# STM32_Schematic.net
KiCad netlist of a schematic drawn in Altium Designer
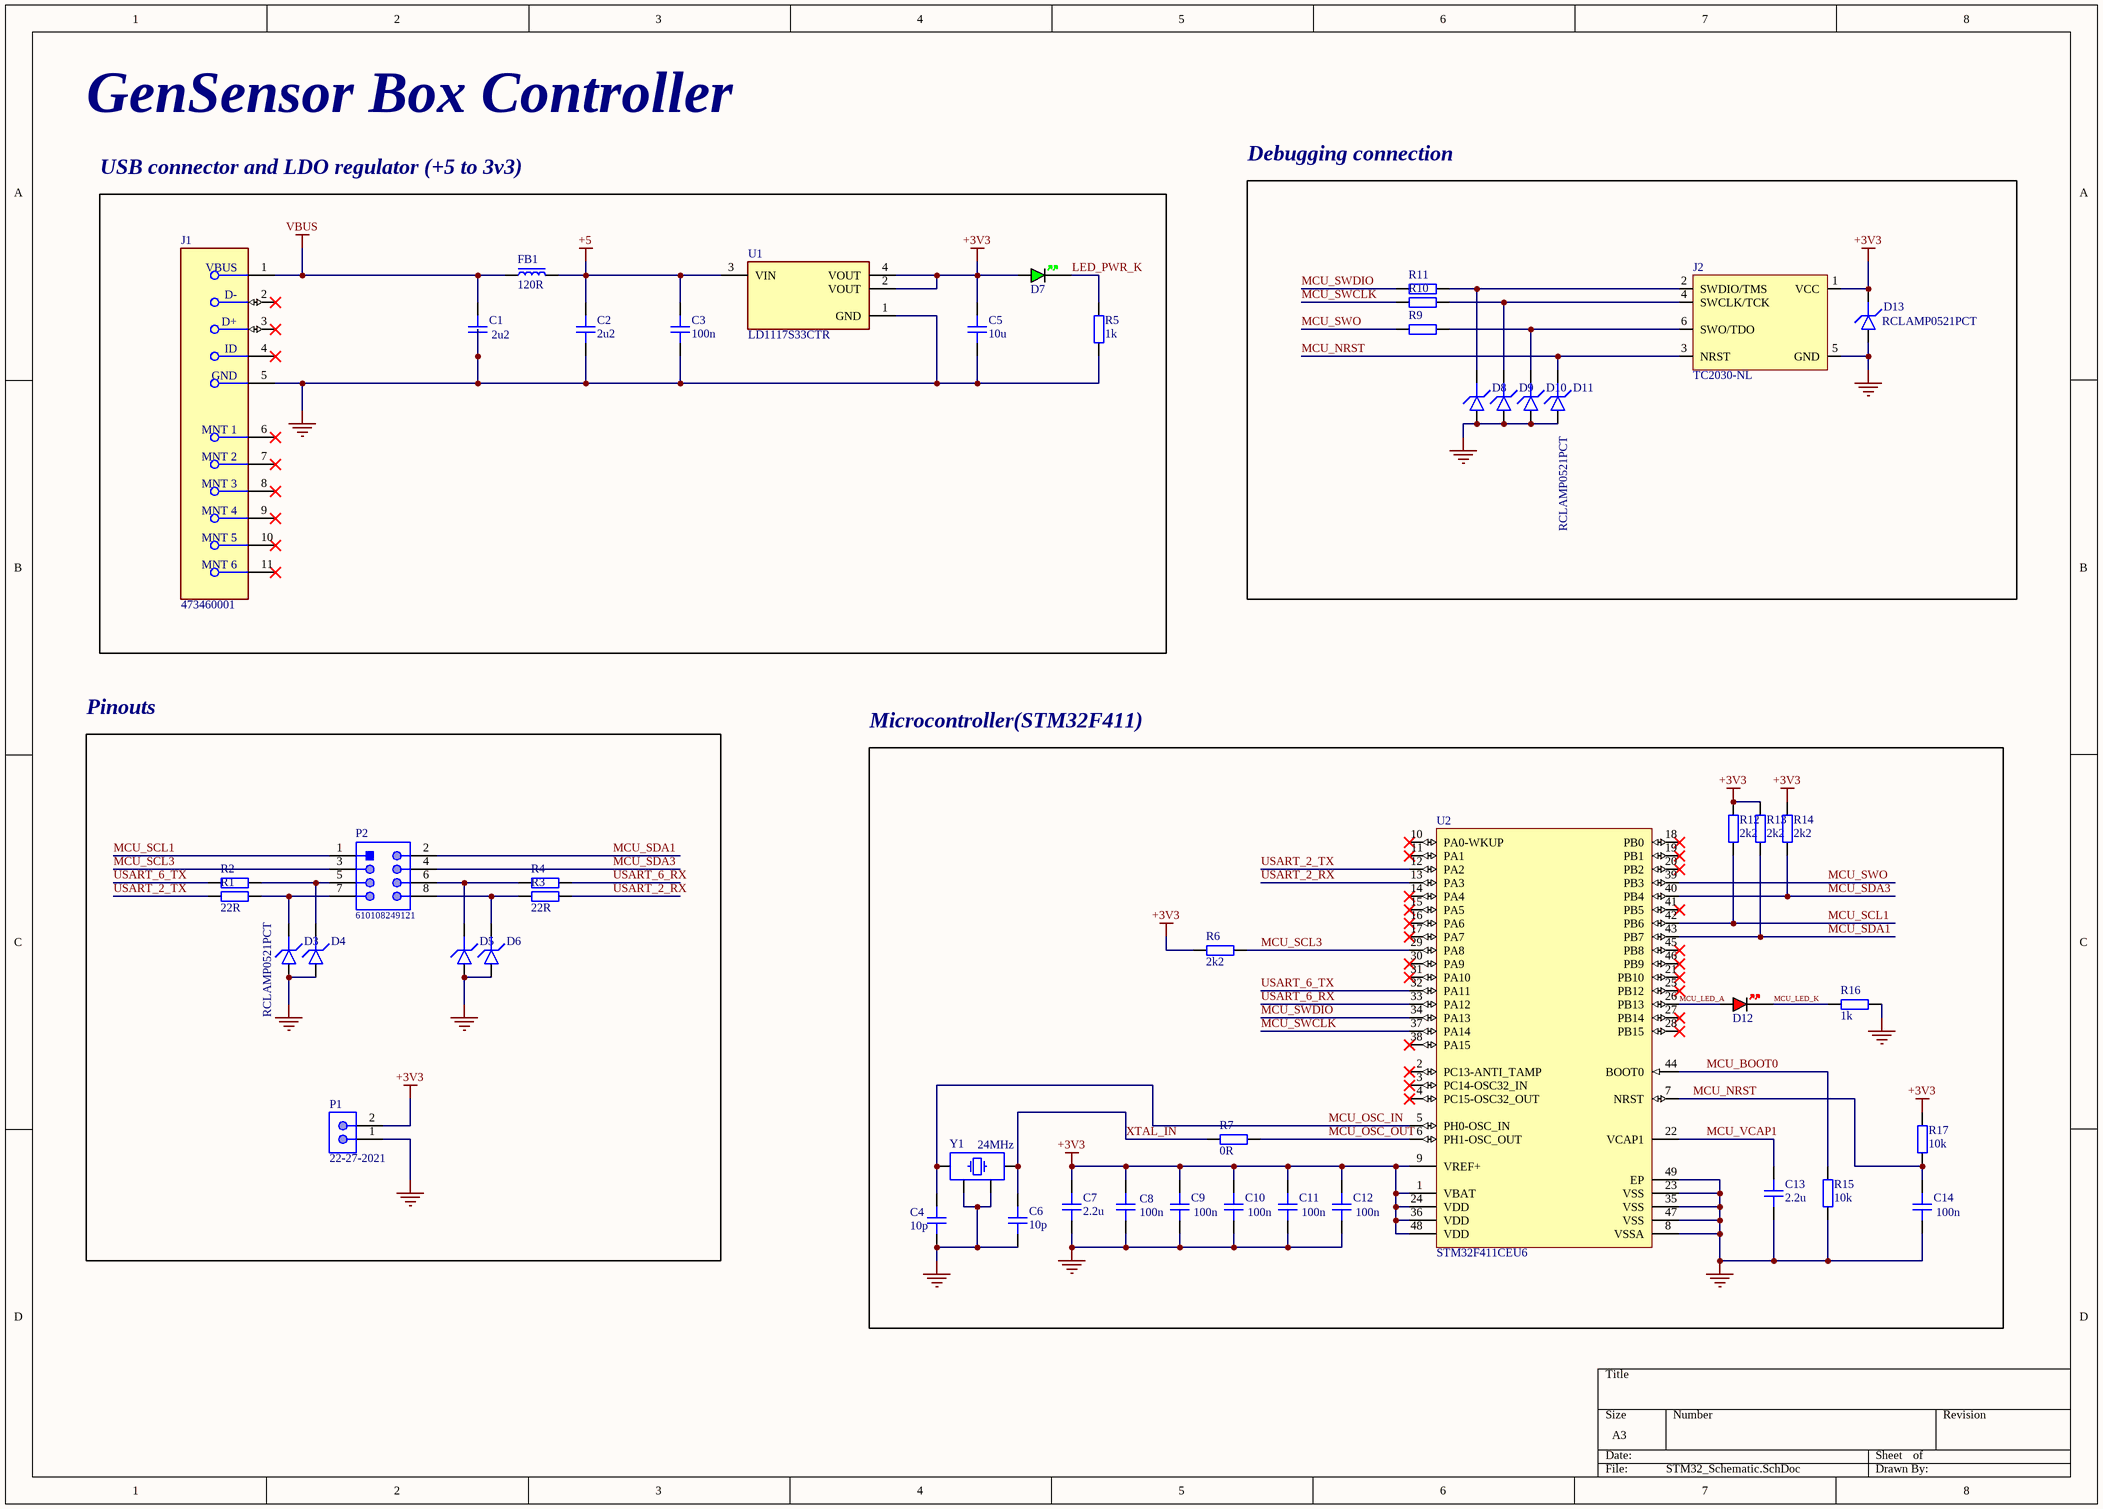
[diagram p0: STM32_Schematic.SchDoc]

(export (version "E")
  (design (tool "Eeschema 10.0.6"))
  (components
    (comp (ref "C1")
      (value "2u2")
      (footprint "CAP_0603")
      (description "Capacitor SMD 0603 16V")
      (libsource (lib "Schematic-Lib-PhilsLab") (part "CAP_0603_16V"))
    )
    (comp (ref "C2")
      (value "2u2")
      (footprint "CAP_0603")
      (description "Capacitor SMD 0603 16V")
      (libsource (lib "Schematic-Lib-PhilsLab") (part "CAP_0603_16V"))
    )
    (comp (ref "C3")
      (value "100n")
      (footprint "CAP_0805")
      (description "Capacitor SMD 0805 16V")
      (libsource (lib "Schematic-Lib-PhilsLab") (part "CAP_0805_16V"))
    )
    (comp (ref "C4")
      (value "10p")
      (footprint "CAP_0402")
      (description "Capacitor SMD 0402 16V")
      (libsource (lib "Schematic-Lib-PhilsLab") (part "CAP_0402_16V"))
    )
    (comp (ref "C5")
      (value "10u")
      (footprint "CAP_0805")
      (description "Capacitor SMD 0805 16V")
      (libsource (lib "Schematic-Lib-PhilsLab") (part "CAP_0805_16V"))
    )
    (comp (ref "C6")
      (value "10p")
      (footprint "CAP_0402")
      (description "Capacitor SMD 0402 16V")
      (libsource (lib "Schematic-Lib-PhilsLab") (part "CAP_0402_16V"))
    )
    (comp (ref "C7")
      (value "2.2u")
      (footprint "CAP_0603")
      (description "Capacitor SMD 0603 16V")
      (libsource (lib "Schematic-Lib-PhilsLab") (part "CAP_0603_16V"))
    )
    (comp (ref "C8")
      (value "100n")
      (footprint "CAP_0402")
      (description "Capacitor SMD 0402 16V")
      (libsource (lib "Schematic-Lib-PhilsLab") (part "CAP_0402_16V"))
    )
    (comp (ref "C9")
      (value "100n")
      (footprint "CAP_0402")
      (description "Capacitor SMD 0402 16V")
      (libsource (lib "Schematic-Lib-PhilsLab") (part "CAP_0402_16V"))
    )
    (comp (ref "C10")
      (value "100n")
      (footprint "CAP_0402")
      (description "Capacitor SMD 0402 16V")
      (libsource (lib "Schematic-Lib-PhilsLab") (part "CAP_0402_16V"))
    )
    (comp (ref "C11")
      (value "100n")
      (footprint "CAP_0402")
      (description "Capacitor SMD 0402 16V")
      (libsource (lib "Schematic-Lib-PhilsLab") (part "CAP_0402_16V"))
    )
    (comp (ref "C12")
      (value "100n")
      (footprint "CAP_0402")
      (description "Capacitor SMD 0402 16V")
      (libsource (lib "Schematic-Lib-PhilsLab") (part "CAP_0402_16V"))
    )
    (comp (ref "C13")
      (value "2.2u")
      (footprint "CAP_0603")
      (description "Capacitor SMD 0603 16V")
      (libsource (lib "Schematic-Lib-PhilsLab") (part "CAP_0603_16V"))
    )
    (comp (ref "C14")
      (value "100n")
      (footprint "CAP_0402")
      (description "Capacitor SMD 0402 16V")
      (libsource (lib "Schematic-Lib-PhilsLab") (part "CAP_0402_16V"))
    )
    (comp (ref "D3")
      (value "RCLAMP0521PCT")
      (footprint "D_0402")
      (description "Diode TVS / ESD 0402")
      (libsource (lib "Schematic-Lib-PhilsLab") (part "D_TVS_0402"))
    )
    (comp (ref "D4")
      (value "RCLAMP0521PCT")
      (footprint "D_0402")
      (description "Diode TVS / ESD 0402")
      (libsource (lib "Schematic-Lib-PhilsLab") (part "D_TVS_0402"))
    )
    (comp (ref "D5")
      (value "RCLAMP0521PCT")
      (footprint "D_0402")
      (description "Diode TVS / ESD 0402")
      (libsource (lib "Schematic-Lib-PhilsLab") (part "D_TVS_0402"))
    )
    (comp (ref "D6")
      (value "RCLAMP0521PCT")
      (footprint "D_0402")
      (description "Diode TVS / ESD 0402")
      (libsource (lib "Schematic-Lib-PhilsLab") (part "D_TVS_0402"))
    )
    (comp (ref "D7")
      (value "GREEN")
      (footprint "LED_0402_GREEN")
      (description "LED 0402 GREEN SMD")
      (libsource (lib "Schematic-Lib-PhilsLab") (part "LED_0402_GREEN"))
    )
    (comp (ref "D8")
      (value "RCLAMP0521PCT")
      (footprint "D_0402")
      (description "Diode TVS / ESD 0402")
      (libsource (lib "Schematic-Lib-PhilsLab") (part "D_TVS_0402"))
    )
    (comp (ref "D9")
      (value "RCLAMP0521PCT")
      (footprint "D_0402")
      (description "Diode TVS / ESD 0402")
      (libsource (lib "Schematic-Lib-PhilsLab") (part "D_TVS_0402"))
    )
    (comp (ref "D10")
      (value "RCLAMP0521PCT")
      (footprint "D_0402")
      (description "Diode TVS / ESD 0402")
      (libsource (lib "Schematic-Lib-PhilsLab") (part "D_TVS_0402"))
    )
    (comp (ref "D11")
      (value "RCLAMP0521PCT")
      (footprint "D_0402")
      (description "Diode TVS / ESD 0402")
      (libsource (lib "Schematic-Lib-PhilsLab") (part "D_TVS_0402"))
    )
    (comp (ref "D12")
      (value "RED")
      (footprint "LED_0402_RED")
      (description "LED 0402 RED SMD")
      (libsource (lib "Schematic-Lib-PhilsLab") (part "LED_0402_RED"))
    )
    (comp (ref "D13")
      (value "RCLAMP0521PCT")
      (footprint "D_0402")
      (description "Diode TVS / ESD 0402")
      (libsource (lib "Schematic-Lib-PhilsLab") (part "D_TVS_0402"))
    )
    (comp (ref "FB1")
      (value "120R")
      (footprint "FB_0603")
      (description "Ferrite Bead SMD 0603")
      (libsource (lib "Schematic-Lib-PhilsLab") (part "FB_0603"))
    )
    (comp (ref "J1")
      (value "473460001")
      (footprint "FP-473460001-MFG")
      (description "CONN RCPT USB2.0 MICRO B SMD R/A")
      (fields
        (field (name "OCTOPART") "https://octopart.com/47346-0001-molex-7164928")
        (field (name "MANUFACTURER") "Molex")
      )
      (libsource (lib "Altium Content Vault") (part "53ae1f1d9b557310b43ca686e5bb76a"))
    )
    (comp (ref "J2")
      (value "TC2030-NL")
      (footprint "TC2030-NL-FP")
      (description "Tag-Connect No-Solder SWD Debug Connector (No Legs) DO NOT PLACE")
      (fields
        (field (name "MANUFACTURER") "Tag-Connect")
        (field (name "MANUFACTURER PART NUMBER") "TC2030-NL-FP")
      )
      (libsource (lib "Schematic-Lib-PhilsLab") (part "TC2030-NL"))
    )
    (comp (ref "P1")
      (value "22-27-2021")
      (footprint "MOLX-22-27-2021_V")
      (fields (field (name "MANUFACTURER") "Molex") (field (name "PARTNUMBER") "0022272021"))
      (libsource (lib "Altium Content Vault") (part "CN-1P-M-R2"))
    )
    (comp (ref "P2")
      (value "610108249121")
      (footprint "610108249121")
      (description "SMT Angled Pin Header WR-PHD, Pitch 2.54 mm, Dual Row, 8 pins")
      (fields (field (name "MANUFACTURER") "Wurth Elektronik") (field (name "PUBLISHER") "WurthElektronik"))
      (libsource (lib "Altium Content Vault") (part "WE-CN-2P-M-R8"))
    )
    (comp (ref "R1")
      (value "22R")
      (footprint "RES_0402")
      (description "Resistor SMD 0402")
      (libsource (lib "Schematic-Lib-PhilsLab") (part "RES_0402"))
    )
    (comp (ref "R2")
      (value "22R")
      (footprint "RES_0402")
      (description "Resistor SMD 0402")
      (libsource (lib "Schematic-Lib-PhilsLab") (part "RES_0402"))
    )
    (comp (ref "R3")
      (value "22R")
      (footprint "RES_0402")
      (description "Resistor SMD 0402")
      (libsource (lib "Schematic-Lib-PhilsLab") (part "RES_0402"))
    )
    (comp (ref "R4")
      (value "22R")
      (footprint "RES_0402")
      (description "Resistor SMD 0402")
      (libsource (lib "Schematic-Lib-PhilsLab") (part "RES_0402"))
    )
    (comp (ref "R5")
      (value "1k")
      (footprint "RES_0402")
      (description "Resistor SMD 0402")
      (libsource (lib "Schematic-Lib-PhilsLab") (part "RES_0402"))
    )
    (comp (ref "R6")
      (value "2k2")
      (footprint "RES_0402")
      (description "Resistor SMD 0402")
      (libsource (lib "Schematic-Lib-PhilsLab") (part "RES_0402"))
    )
    (comp (ref "R7")
      (value "0R")
      (footprint "RES_0402")
      (description "Resistor SMD 0402")
      (libsource (lib "Schematic-Lib-PhilsLab") (part "RES_0402"))
    )
    (comp (ref "R9")
      (value "22R")
      (footprint "RES_0402")
      (description "Resistor SMD 0402")
      (libsource (lib "Schematic-Lib-PhilsLab") (part "RES_0402"))
    )
    (comp (ref "R10")
      (value "22R")
      (footprint "RES_0402")
      (description "Resistor SMD 0402")
      (libsource (lib "Schematic-Lib-PhilsLab") (part "RES_0402"))
    )
    (comp (ref "R11")
      (value "22R")
      (footprint "RES_0402")
      (description "Resistor SMD 0402")
      (libsource (lib "Schematic-Lib-PhilsLab") (part "RES_0402"))
    )
    (comp (ref "R12")
      (value "2k2")
      (footprint "RES_0402")
      (description "Resistor SMD 0402")
      (libsource (lib "Schematic-Lib-PhilsLab") (part "RES_0402"))
    )
    (comp (ref "R13")
      (value "2k2")
      (footprint "RES_0402")
      (description "Resistor SMD 0402")
      (libsource (lib "Schematic-Lib-PhilsLab") (part "RES_0402"))
    )
    (comp (ref "R14")
      (value "2k2")
      (footprint "RES_0402")
      (description "Resistor SMD 0402")
      (libsource (lib "Schematic-Lib-PhilsLab") (part "RES_0402"))
    )
    (comp (ref "R15")
      (value "10k")
      (footprint "RES_0402")
      (description "Resistor SMD 0402")
      (libsource (lib "Schematic-Lib-PhilsLab") (part "RES_0402"))
    )
    (comp (ref "R16")
      (value "1k")
      (footprint "RES_0402")
      (description "Resistor SMD 0402")
      (libsource (lib "Schematic-Lib-PhilsLab") (part "RES_0402"))
    )
    (comp (ref "R17")
      (value "10k")
      (footprint "RES_0402")
      (description "Resistor SMD 0402")
      (libsource (lib "Schematic-Lib-PhilsLab") (part "RES_0402"))
    )
    (comp (ref "U1")
      (value "LD1117S33CTR")
      (footprint "FP-SOT-223-0046067_14-MFG")
      (description "IC REG LINEAR 3.3V 800MA SOT223")
      (libsource (lib "Altium Content Vault") (part "7818869c5c16ceab15634627166a29d"))
    )
    (comp (ref "U2")
      (value "STM32F411CEU6")
      (footprint "STM-UFQFPN48_L")
      (libsource (lib "Altium Content Vault") (part "MC-ARM-STM32F411-UFQFPN48"))
    )
    (comp (ref "Y1")
      (value "24MHz")
      (footprint "XTAL_3225")
      (description "Crystal SMD 24MHz 10PPM 7pF 3225")
      (fields (field (name "MANUFACTURER") "Epson"))
      (libsource (lib "Schematic-Lib-PhilsLab") (part "TSX-3225_24.0000MF15X-AC"))
    )
  )
  (nets
    (net (code "1") (name "+3V3") (class "Default")
      (node (ref "C10") (pin "2") (pinfunction "2_2") (pintype "passive"))
      (node (ref "C11") (pin "2") (pinfunction "2_2") (pintype "passive"))
      (node (ref "C12") (pin "2") (pinfunction "2_2") (pintype "passive"))
      (node (ref "C5") (pin "2") (pinfunction "2_2") (pintype "passive"))
      (node (ref "C7") (pin "2") (pinfunction "2_2") (pintype "passive"))
      (node (ref "C8") (pin "2") (pinfunction "2_2") (pintype "passive"))
      (node (ref "C9") (pin "2") (pinfunction "2_2") (pintype "passive"))
      (node (ref "D13") (pin "K") (pinfunction "K_K") (pintype "passive"))
      (node (ref "D7") (pin "A") (pinfunction "A_A") (pintype "passive"))
      (node (ref "J2") (pin "1") (pinfunction "VCC_1") (pintype "passive"))
      (node (ref "P1") (pin "2") (pinfunction "2_2") (pintype "passive"))
      (node (ref "R12") (pin "2") (pinfunction "2_2") (pintype "passive"))
      (node (ref "R13") (pin "2") (pinfunction "2_2") (pintype "passive"))
      (node (ref "R14") (pin "2") (pinfunction "2_2") (pintype "passive"))
      (node (ref "R17") (pin "2") (pinfunction "2_2") (pintype "passive"))
      (node (ref "R6") (pin "2") (pinfunction "2_2") (pintype "passive"))
      (node (ref "U1") (pin "2") (pinfunction "VOUT_2") (pintype "power_in"))
      (node (ref "U1") (pin "4") (pinfunction "VOUT_4") (pintype "power_in"))
      (node (ref "U2") (pin "1") (pinfunction "VBAT_1") (pintype "power_in"))
      (node (ref "U2") (pin "24") (pinfunction "VDD_24") (pintype "power_in"))
      (node (ref "U2") (pin "36") (pinfunction "VDD_36") (pintype "power_in"))
      (node (ref "U2") (pin "48") (pinfunction "VDD_48") (pintype "power_in"))
      (node (ref "U2") (pin "9") (pinfunction "VREF+_9") (pintype "power_in"))
    )
    (net (code "2") (name "+5") (class "Default")
      (node (ref "C2") (pin "2") (pinfunction "2_2") (pintype "passive"))
      (node (ref "C3") (pin "2") (pinfunction "2_2") (pintype "passive"))
      (node (ref "FB1") (pin "2") (pinfunction "2_2") (pintype "passive"))
      (node (ref "U1") (pin "3") (pinfunction "VIN_3") (pintype "power_in"))
    )
    (net (code "3") (name "/LED_PWR_K") (class "Default")
      (node (ref "D7") (pin "K") (pinfunction "K_K") (pintype "passive"))
      (node (ref "R5") (pin "2") (pinfunction "2_2") (pintype "passive"))
    )
    (net (code "4") (name "/MCU_BOOT0") (class "Default")
      (node (ref "R15") (pin "2") (pinfunction "2_2") (pintype "passive"))
      (node (ref "U2") (pin "44") (pinfunction "BOOT0_44") (pintype "input"))
    )
    (net (code "5") (name "/MCU_LED_A") (class "Default")
      (node (ref "D12") (pin "A") (pinfunction "A_A") (pintype "passive"))
      (node (ref "U2") (pin "26") (pinfunction "PB13_26") (pintype "bidirectional"))
    )
    (net (code "6") (name "/MCU_LED_K") (class "Default")
      (node (ref "D12") (pin "K") (pinfunction "K_K") (pintype "passive"))
      (node (ref "R16") (pin "2") (pinfunction "2_2") (pintype "passive"))
    )
    (net (code "7") (name "/MCU_NRST") (class "Default")
      (node (ref "C14") (pin "2") (pinfunction "2_2") (pintype "passive"))
      (node (ref "D11") (pin "K") (pinfunction "K_K") (pintype "passive"))
      (node (ref "J2") (pin "3") (pinfunction "NRST_3") (pintype "passive"))
      (node (ref "R17") (pin "1") (pinfunction "1_1") (pintype "passive"))
      (node (ref "U2") (pin "7") (pinfunction "NRST_7") (pintype "bidirectional"))
    )
    (net (code "8") (name "/MCU_OSC_IN") (class "Default")
      (node (ref "C4") (pin "2") (pinfunction "2_2") (pintype "passive"))
      (node (ref "U2") (pin "5") (pinfunction "PH0-OSC_IN_5") (pintype "bidirectional"))
      (node (ref "Y1") (pin "1") (pinfunction "1_1") (pintype "passive"))
    )
    (net (code "9") (name "/MCU_OSC_OUT") (class "Default")
      (node (ref "R7") (pin "2") (pinfunction "2_2") (pintype "passive"))
      (node (ref "U2") (pin "6") (pinfunction "PH1-OSC_OUT_6") (pintype "bidirectional"))
    )
    (net (code "10") (name "/MCU_SCL1") (class "Default")
      (node (ref "P2") (pin "1") (pinfunction "1_1") (pintype "passive"))
      (node (ref "R12") (pin "1") (pinfunction "1_1") (pintype "passive"))
      (node (ref "U2") (pin "42") (pinfunction "PB6_42") (pintype "bidirectional"))
    )
    (net (code "11") (name "/MCU_SCL3") (class "Default")
      (node (ref "P2") (pin "3") (pinfunction "3_3") (pintype "passive"))
      (node (ref "R6") (pin "1") (pinfunction "1_1") (pintype "passive"))
      (node (ref "U2") (pin "29") (pinfunction "PA8_29") (pintype "bidirectional"))
    )
    (net (code "12") (name "/MCU_SDA1") (class "Default")
      (node (ref "P2") (pin "2") (pinfunction "2_2") (pintype "passive"))
      (node (ref "R13") (pin "1") (pinfunction "1_1") (pintype "passive"))
      (node (ref "U2") (pin "43") (pinfunction "PB7_43") (pintype "bidirectional"))
    )
    (net (code "13") (name "/MCU_SDA3") (class "Default")
      (node (ref "P2") (pin "4") (pinfunction "4_4") (pintype "passive"))
      (node (ref "R14") (pin "1") (pinfunction "1_1") (pintype "passive"))
      (node (ref "U2") (pin "40") (pinfunction "PB4_40") (pintype "bidirectional"))
    )
    (net (code "14") (name "/MCU_SWCLK") (class "Default")
      (node (ref "R10") (pin "2") (pinfunction "2_2") (pintype "passive"))
      (node (ref "U2") (pin "37") (pinfunction "PA14_37") (pintype "bidirectional"))
    )
    (net (code "15") (name "/MCU_SWDIO") (class "Default")
      (node (ref "R11") (pin "2") (pinfunction "2_2") (pintype "passive"))
      (node (ref "U2") (pin "34") (pinfunction "PA13_34") (pintype "bidirectional"))
    )
    (net (code "16") (name "/MCU_SWO") (class "Default")
      (node (ref "R9") (pin "2") (pinfunction "2_2") (pintype "passive"))
      (node (ref "U2") (pin "39") (pinfunction "PB3_39") (pintype "bidirectional"))
    )
    (net (code "17") (name "/MCU_VCAP1") (class "Default")
      (node (ref "C13") (pin "2") (pinfunction "2_2") (pintype "passive"))
      (node (ref "U2") (pin "22") (pinfunction "VCAP1_22") (pintype "passive"))
    )
    (net (code "18") (name "/USART_2_RX") (class "Default")
      (node (ref "R3") (pin "1") (pinfunction "1_1") (pintype "passive"))
      (node (ref "U2") (pin "13") (pinfunction "PA3_13") (pintype "bidirectional"))
    )
    (net (code "19") (name "/USART_2_TX") (class "Default")
      (node (ref "R1") (pin "2") (pinfunction "2_2") (pintype "passive"))
      (node (ref "U2") (pin "12") (pinfunction "PA2_12") (pintype "bidirectional"))
    )
    (net (code "20") (name "/USART_6_RX") (class "Default")
      (node (ref "R4") (pin "1") (pinfunction "1_1") (pintype "passive"))
      (node (ref "U2") (pin "33") (pinfunction "PA12_33") (pintype "bidirectional"))
    )
    (net (code "21") (name "/USART_6_TX") (class "Default")
      (node (ref "R2") (pin "2") (pinfunction "2_2") (pintype "passive"))
      (node (ref "U2") (pin "32") (pinfunction "PA11_32") (pintype "bidirectional"))
    )
    (net (code "22") (name "/XTAL_IN") (class "Default")
      (node (ref "C6") (pin "2") (pinfunction "2_2") (pintype "passive"))
      (node (ref "R7") (pin "1") (pinfunction "1_1") (pintype "passive"))
      (node (ref "Y1") (pin "3") (pinfunction "3_3") (pintype "passive"))
    )
    (net (code "23") (name "GND") (class "Default")
      (node (ref "C1") (pin "1") (pinfunction "1_1") (pintype "passive"))
      (node (ref "C10") (pin "1") (pinfunction "1_1") (pintype "passive"))
      (node (ref "C11") (pin "1") (pinfunction "1_1") (pintype "passive"))
      (node (ref "C12") (pin "1") (pinfunction "1_1") (pintype "passive"))
      (node (ref "C13") (pin "1") (pinfunction "1_1") (pintype "passive"))
      (node (ref "C14") (pin "1") (pinfunction "1_1") (pintype "passive"))
      (node (ref "C2") (pin "1") (pinfunction "1_1") (pintype "passive"))
      (node (ref "C3") (pin "1") (pinfunction "1_1") (pintype "passive"))
      (node (ref "C4") (pin "1") (pinfunction "1_1") (pintype "passive"))
      (node (ref "C5") (pin "1") (pinfunction "1_1") (pintype "passive"))
      (node (ref "C6") (pin "1") (pinfunction "1_1") (pintype "passive"))
      (node (ref "C7") (pin "1") (pinfunction "1_1") (pintype "passive"))
      (node (ref "C8") (pin "1") (pinfunction "1_1") (pintype "passive"))
      (node (ref "C9") (pin "1") (pinfunction "1_1") (pintype "passive"))
      (node (ref "D10") (pin "A") (pinfunction "A_A") (pintype "passive"))
      (node (ref "D11") (pin "A") (pinfunction "A_A") (pintype "passive"))
      (node (ref "D13") (pin "A") (pinfunction "A_A") (pintype "passive"))
      (node (ref "D3") (pin "A") (pinfunction "A_A") (pintype "passive"))
      (node (ref "D4") (pin "A") (pinfunction "A_A") (pintype "passive"))
      (node (ref "D5") (pin "A") (pinfunction "A_A") (pintype "passive"))
      (node (ref "D6") (pin "A") (pinfunction "A_A") (pintype "passive"))
      (node (ref "D8") (pin "A") (pinfunction "A_A") (pintype "passive"))
      (node (ref "D9") (pin "A") (pinfunction "A_A") (pintype "passive"))
      (node (ref "J1") (pin "5") (pinfunction "GND_5") (pintype "power_in"))
      (node (ref "J2") (pin "5") (pinfunction "GND_5") (pintype "passive"))
      (node (ref "P1") (pin "1") (pinfunction "1_1") (pintype "passive"))
      (node (ref "R15") (pin "1") (pinfunction "1_1") (pintype "passive"))
      (node (ref "R16") (pin "1") (pinfunction "1_1") (pintype "passive"))
      (node (ref "R5") (pin "1") (pinfunction "1_1") (pintype "passive"))
      (node (ref "U1") (pin "1") (pinfunction "GND_1") (pintype "power_in"))
      (node (ref "U2") (pin "23") (pinfunction "VSS_23") (pintype "power_in"))
      (node (ref "U2") (pin "35") (pinfunction "VSS_35") (pintype "power_in"))
      (node (ref "U2") (pin "47") (pinfunction "VSS_47") (pintype "power_in"))
      (node (ref "U2") (pin "49") (pinfunction "EP_49") (pintype "power_in"))
      (node (ref "U2") (pin "8") (pinfunction "VSSA_8") (pintype "power_in"))
      (node (ref "Y1") (pin "2") (pinfunction "2_2") (pintype "passive"))
      (node (ref "Y1") (pin "4") (pinfunction "4_4") (pintype "passive"))
    )
    (net (code "24") (name "Net-(D3-PadK)") (class "Default")
      (node (ref "D3") (pin "K") (pinfunction "K_K") (pintype "passive"))
      (node (ref "P2") (pin "7") (pinfunction "7_7") (pintype "passive"))
      (node (ref "R1") (pin "1") (pinfunction "1_1") (pintype "passive"))
    )
    (net (code "25") (name "Net-(D4-PadK)") (class "Default")
      (node (ref "D4") (pin "K") (pinfunction "K_K") (pintype "passive"))
      (node (ref "P2") (pin "5") (pinfunction "5_5") (pintype "passive"))
      (node (ref "R2") (pin "1") (pinfunction "1_1") (pintype "passive"))
    )
    (net (code "26") (name "Net-(D5-PadK)") (class "Default")
      (node (ref "D5") (pin "K") (pinfunction "K_K") (pintype "passive"))
      (node (ref "P2") (pin "6") (pinfunction "6_6") (pintype "passive"))
      (node (ref "R4") (pin "2") (pinfunction "2_2") (pintype "passive"))
    )
    (net (code "27") (name "Net-(D6-PadK)") (class "Default")
      (node (ref "D6") (pin "K") (pinfunction "K_K") (pintype "passive"))
      (node (ref "P2") (pin "8") (pinfunction "8_8") (pintype "passive"))
      (node (ref "R3") (pin "2") (pinfunction "2_2") (pintype "passive"))
    )
    (net (code "28") (name "Net-(J2-SWCLK{slash}TCK)") (class "Default")
      (node (ref "D9") (pin "K") (pinfunction "K_K") (pintype "passive"))
      (node (ref "J2") (pin "4") (pinfunction "SWCLK/TCK_4") (pintype "passive"))
      (node (ref "R10") (pin "1") (pinfunction "1_1") (pintype "passive"))
    )
    (net (code "29") (name "Net-(J2-SWDIO{slash}TMS)") (class "Default")
      (node (ref "D8") (pin "K") (pinfunction "K_K") (pintype "passive"))
      (node (ref "J2") (pin "2") (pinfunction "SWDIO/TMS_2") (pintype "passive"))
      (node (ref "R11") (pin "1") (pinfunction "1_1") (pintype "passive"))
    )
    (net (code "30") (name "Net-(J2-SWO{slash}TDO)") (class "Default")
      (node (ref "D10") (pin "K") (pinfunction "K_K") (pintype "passive"))
      (node (ref "J2") (pin "6") (pinfunction "SWO/TDO_6") (pintype "passive"))
      (node (ref "R9") (pin "1") (pinfunction "1_1") (pintype "passive"))
    )
    (net (code "31") (name "VBUS") (class "Default")
      (node (ref "C1") (pin "2") (pinfunction "2_2") (pintype "passive"))
      (node (ref "FB1") (pin "1") (pinfunction "1_1") (pintype "passive"))
      (node (ref "J1") (pin "1") (pinfunction "VBUS_1") (pintype "power_in"))
    )
    (net (code "32") (name "unconnected-(J1-D+-Pad3)") (class "Default")
      (node (ref "J1") (pin "3") (pinfunction "D+_3") (pintype "bidirectional+no_connect"))
    )
    (net (code "33") (name "unconnected-(J1-D--Pad2)") (class "Default")
      (node (ref "J1") (pin "2") (pinfunction "D-_2") (pintype "bidirectional+no_connect"))
    )
    (net (code "34") (name "unconnected-(J1-ID-Pad4)") (class "Default")
      (node (ref "J1") (pin "4") (pinfunction "ID_4") (pintype "passive+no_connect"))
    )
    (net (code "35") (name "unconnected-(J1-MNT_1-Pad6)") (class "Default")
      (node (ref "J1") (pin "6") (pinfunction "MNT_1_6") (pintype "passive+no_connect"))
    )
    (net (code "36") (name "unconnected-(J1-MNT_2-Pad7)") (class "Default")
      (node (ref "J1") (pin "7") (pinfunction "MNT_2_7") (pintype "passive+no_connect"))
    )
    (net (code "37") (name "unconnected-(J1-MNT_3-Pad8)") (class "Default")
      (node (ref "J1") (pin "8") (pinfunction "MNT_3_8") (pintype "passive+no_connect"))
    )
    (net (code "38") (name "unconnected-(J1-MNT_4-Pad9)") (class "Default")
      (node (ref "J1") (pin "9") (pinfunction "MNT_4_9") (pintype "passive+no_connect"))
    )
    (net (code "39") (name "unconnected-(J1-MNT_5-Pad10)") (class "Default")
      (node (ref "J1") (pin "10") (pinfunction "MNT_5_10") (pintype "passive+no_connect"))
    )
    (net (code "40") (name "unconnected-(J1-MNT_6-Pad11)") (class "Default")
      (node (ref "J1") (pin "11") (pinfunction "MNT_6_11") (pintype "passive+no_connect"))
    )
    (net (code "41") (name "unconnected-(U2-PA0-WKUP-Pad10)") (class "Default")
      (node (ref "U2") (pin "10") (pinfunction "PA0-WKUP_10") (pintype "bidirectional+no_connect"))
    )
    (net (code "42") (name "unconnected-(U2-PA1-Pad11)") (class "Default")
      (node (ref "U2") (pin "11") (pinfunction "PA1_11") (pintype "bidirectional+no_connect"))
    )
    (net (code "43") (name "unconnected-(U2-PA4-Pad14)") (class "Default")
      (node (ref "U2") (pin "14") (pinfunction "PA4_14") (pintype "bidirectional+no_connect"))
    )
    (net (code "44") (name "unconnected-(U2-PA5-Pad15)") (class "Default")
      (node (ref "U2") (pin "15") (pinfunction "PA5_15") (pintype "bidirectional+no_connect"))
    )
    (net (code "45") (name "unconnected-(U2-PA6-Pad16)") (class "Default")
      (node (ref "U2") (pin "16") (pinfunction "PA6_16") (pintype "bidirectional+no_connect"))
    )
    (net (code "46") (name "unconnected-(U2-PA7-Pad17)") (class "Default")
      (node (ref "U2") (pin "17") (pinfunction "PA7_17") (pintype "bidirectional+no_connect"))
    )
    (net (code "47") (name "unconnected-(U2-PA9-Pad30)") (class "Default")
      (node (ref "U2") (pin "30") (pinfunction "PA9_30") (pintype "bidirectional+no_connect"))
    )
    (net (code "48") (name "unconnected-(U2-PA10-Pad31)") (class "Default")
      (node (ref "U2") (pin "31") (pinfunction "PA10_31") (pintype "bidirectional+no_connect"))
    )
    (net (code "49") (name "unconnected-(U2-PA15-Pad38)") (class "Default")
      (node (ref "U2") (pin "38") (pinfunction "PA15_38") (pintype "bidirectional+no_connect"))
    )
    (net (code "50") (name "unconnected-(U2-PB0-Pad18)") (class "Default")
      (node (ref "U2") (pin "18") (pinfunction "PB0_18") (pintype "bidirectional+no_connect"))
    )
    (net (code "51") (name "unconnected-(U2-PB1-Pad19)") (class "Default")
      (node (ref "U2") (pin "19") (pinfunction "PB1_19") (pintype "bidirectional+no_connect"))
    )
    (net (code "52") (name "unconnected-(U2-PB2-Pad20)") (class "Default")
      (node (ref "U2") (pin "20") (pinfunction "PB2_20") (pintype "bidirectional+no_connect"))
    )
    (net (code "53") (name "unconnected-(U2-PB5-Pad41)") (class "Default")
      (node (ref "U2") (pin "41") (pinfunction "PB5_41") (pintype "bidirectional+no_connect"))
    )
    (net (code "54") (name "unconnected-(U2-PB8-Pad45)") (class "Default")
      (node (ref "U2") (pin "45") (pinfunction "PB8_45") (pintype "bidirectional+no_connect"))
    )
    (net (code "55") (name "unconnected-(U2-PB9-Pad46)") (class "Default")
      (node (ref "U2") (pin "46") (pinfunction "PB9_46") (pintype "bidirectional+no_connect"))
    )
    (net (code "56") (name "unconnected-(U2-PB10-Pad21)") (class "Default")
      (node (ref "U2") (pin "21") (pinfunction "PB10_21") (pintype "bidirectional+no_connect"))
    )
    (net (code "57") (name "unconnected-(U2-PB12-Pad25)") (class "Default")
      (node (ref "U2") (pin "25") (pinfunction "PB12_25") (pintype "bidirectional+no_connect"))
    )
    (net (code "58") (name "unconnected-(U2-PB14-Pad27)") (class "Default")
      (node (ref "U2") (pin "27") (pinfunction "PB14_27") (pintype "bidirectional+no_connect"))
    )
    (net (code "59") (name "unconnected-(U2-PB15-Pad28)") (class "Default")
      (node (ref "U2") (pin "28") (pinfunction "PB15_28") (pintype "bidirectional+no_connect"))
    )
    (net (code "60") (name "unconnected-(U2-PC13-ANTI_TAMP-Pad2)") (class "Default")
      (node (ref "U2") (pin "2") (pinfunction "PC13-ANTI_TAMP_2") (pintype "bidirectional+no_connect"))
    )
    (net (code "61") (name "unconnected-(U2-PC14-OSC32_IN-Pad3)") (class "Default")
      (node (ref "U2") (pin "3") (pinfunction "PC14-OSC32_IN_3") (pintype "bidirectional+no_connect"))
    )
    (net (code "62") (name "unconnected-(U2-PC15-OSC32_OUT-Pad4)") (class "Default")
      (node (ref "U2") (pin "4") (pinfunction "PC15-OSC32_OUT_4") (pintype "bidirectional+no_connect"))
    )
  )
)
